# Motor_Cape.net
KiCad netlist of a schematic drawn in EAGLE
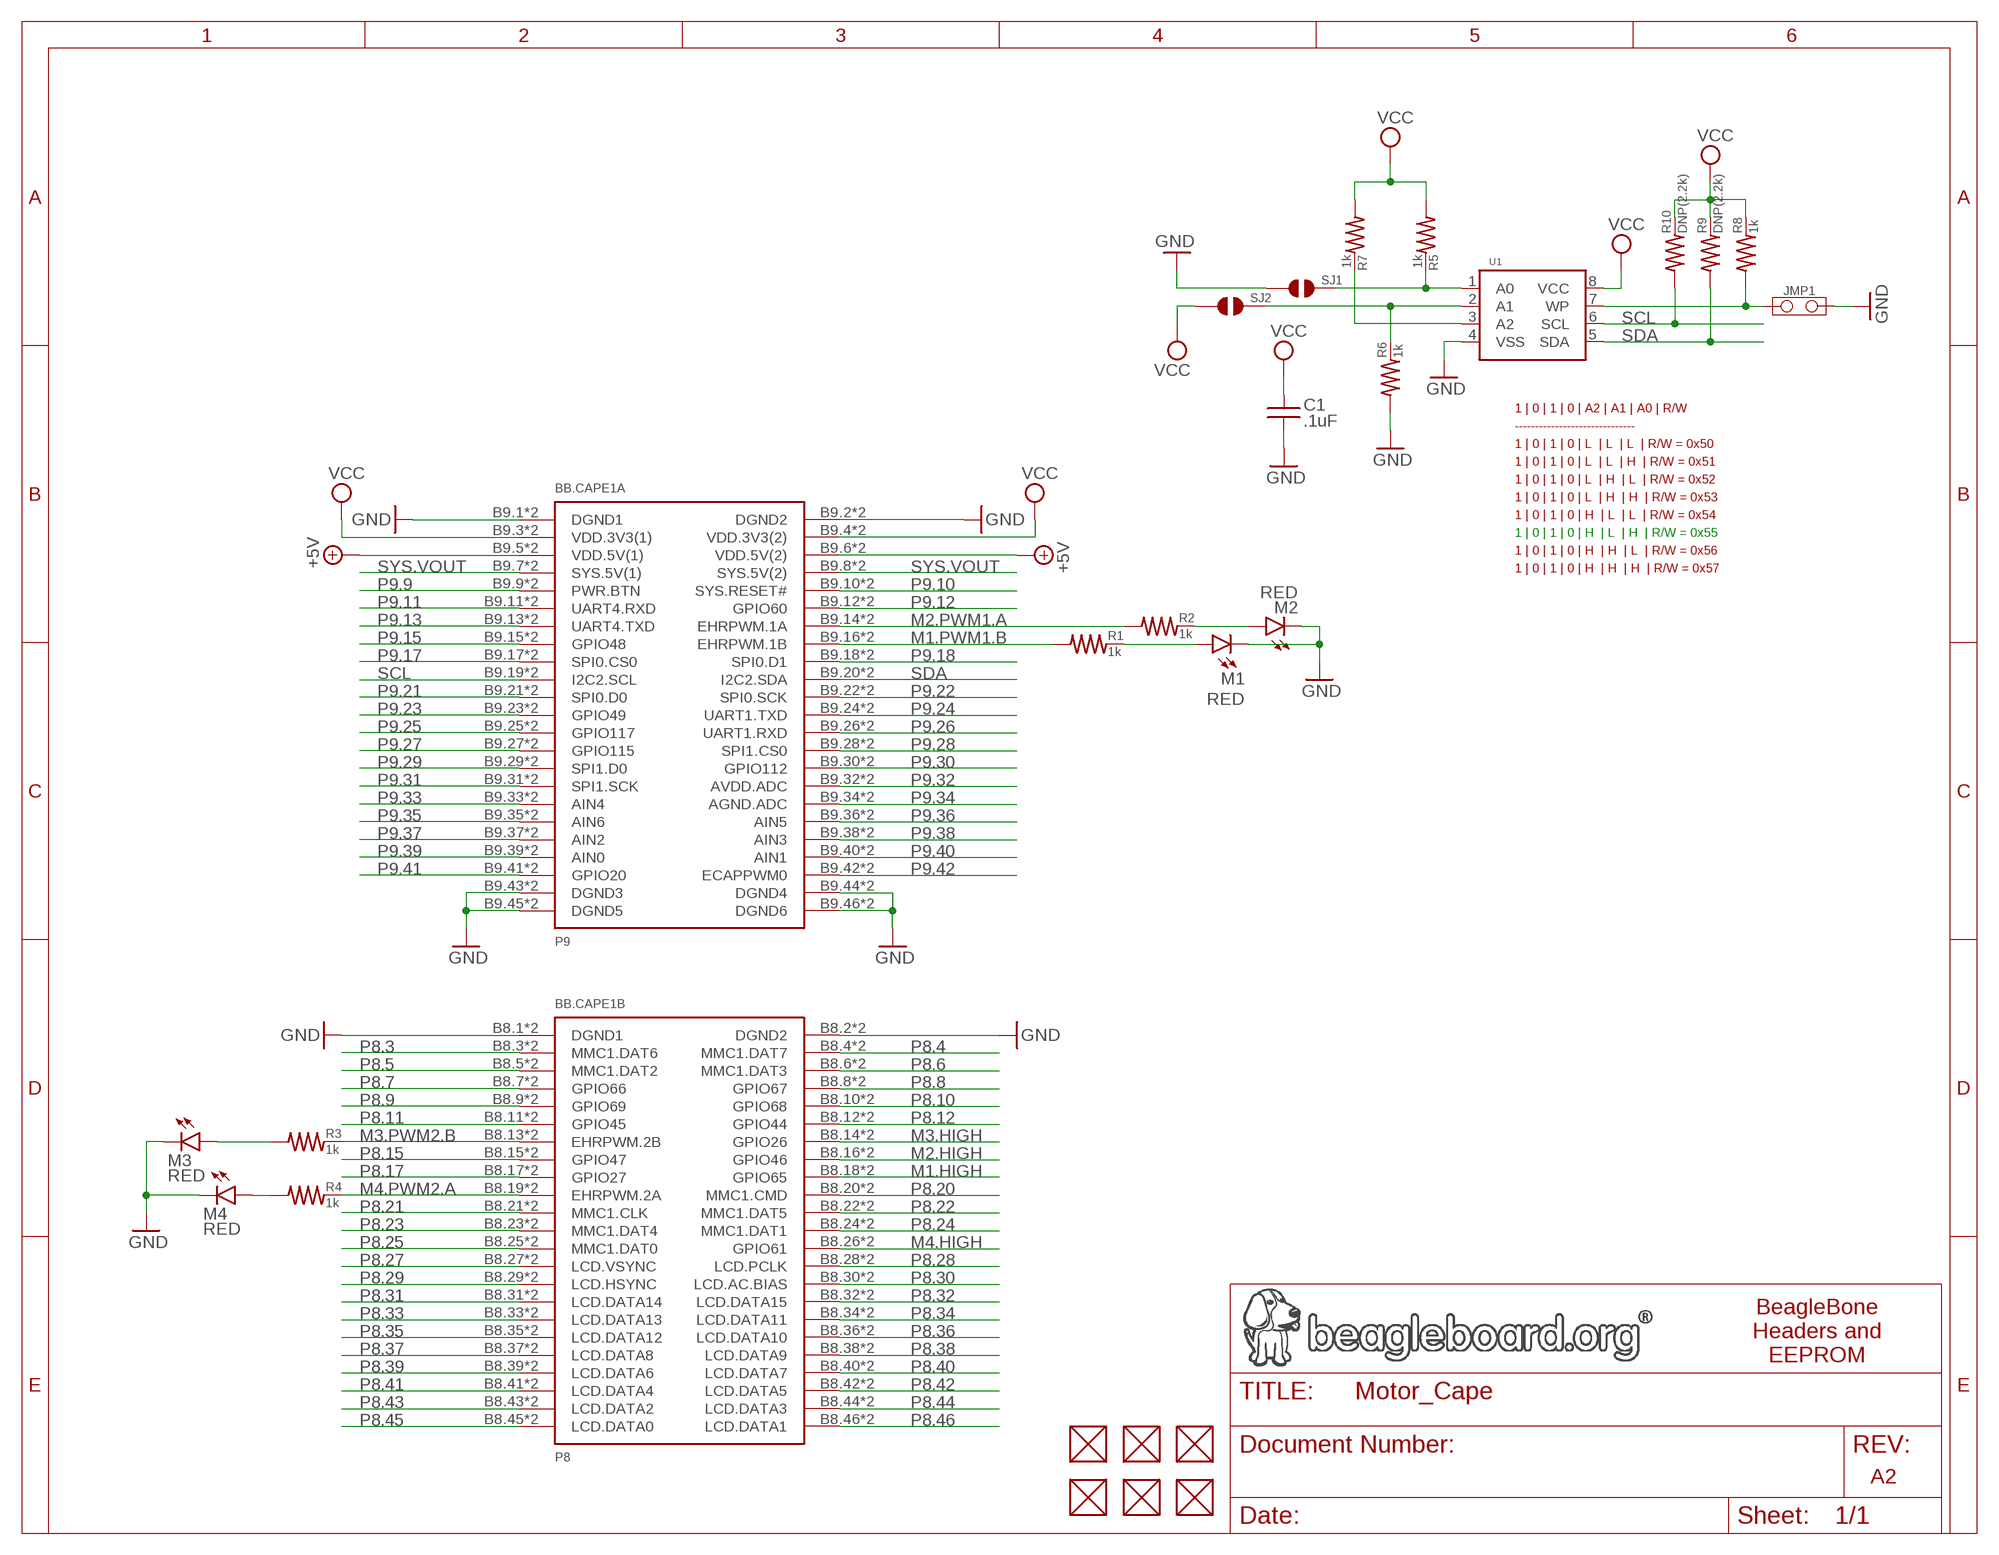
[diagram p0: schematic, sheet 1, part 1 of 2]
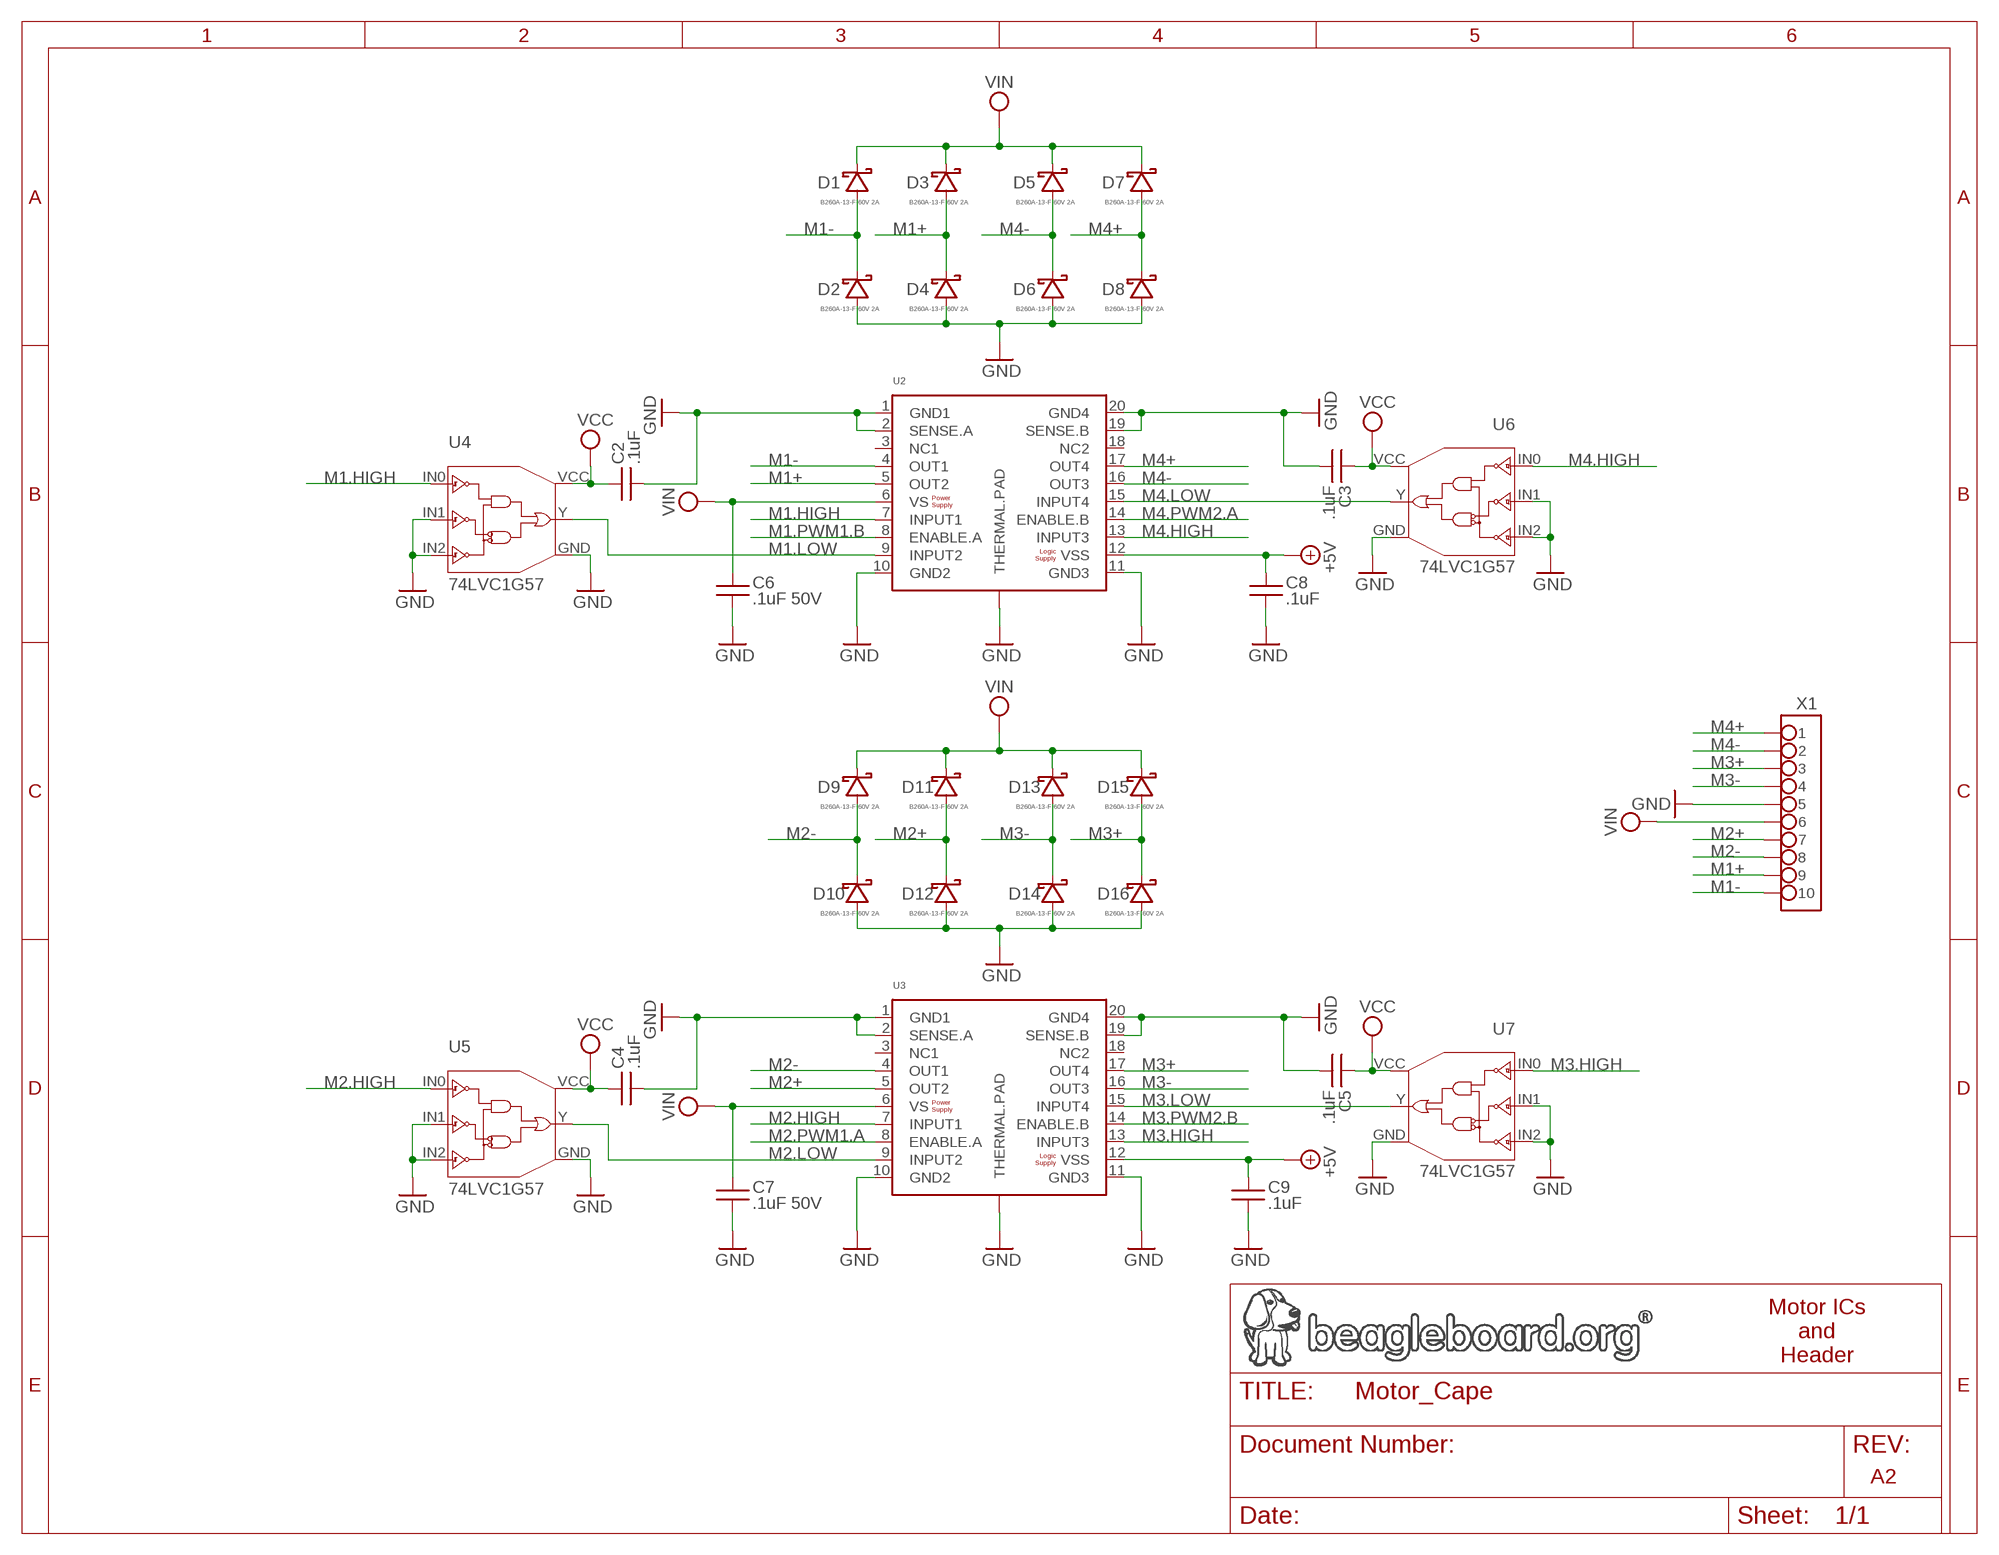
[diagram p1: schematic, sheet 1, part 2 of 2]

(export (version "E")
  (design (tool "Eeschema 10.0.6"))
  (components
    (comp (ref "BB.CAPE1")
      (value "BEAGLEBONE.CAPE.TOP/BOTTOM-PADS")
      (footprint "eagle-import:BEAGLEBONE.CAPE.TOP_BOTTOM-PADS")
      (libsource (lib "eagle-import") (part "BEAGLEBONE.CAPE.TOP/BOTTOM-PADS"))
    )
    (comp (ref "C1")
      (value ".1uF")
      (footprint "eagle-import:0402")
      (libsource (lib "eagle-import") (part "CAPACITOR-(INCH)-0402"))
    )
    (comp (ref "C2")
      (value ".1uF")
      (footprint "eagle-import:0402")
      (libsource (lib "eagle-import") (part "CAPACITOR-(INCH)-0402"))
    )
    (comp (ref "C3")
      (value ".1uF")
      (footprint "eagle-import:0402")
      (libsource (lib "eagle-import") (part "CAPACITOR-(INCH)-0402"))
    )
    (comp (ref "C4")
      (value ".1uF")
      (footprint "eagle-import:0402")
      (libsource (lib "eagle-import") (part "CAPACITOR-(INCH)-0402"))
    )
    (comp (ref "C5")
      (value ".1uF")
      (footprint "eagle-import:0402")
      (libsource (lib "eagle-import") (part "CAPACITOR-(INCH)-0402"))
    )
    (comp (ref "C6")
      (value ".1uF 50V")
      (footprint "eagle-import:0603")
      (libsource (lib "eagle-import") (part "CAPACITOR-(INCH)-0603"))
    )
    (comp (ref "C7")
      (value ".1uF 50V")
      (footprint "eagle-import:0603")
      (libsource (lib "eagle-import") (part "CAPACITOR-(INCH)-0603"))
    )
    (comp (ref "C8")
      (value ".1uF")
      (footprint "eagle-import:0402")
      (libsource (lib "eagle-import") (part "CAPACITOR-(INCH)-0402"))
    )
    (comp (ref "C9")
      (value ".1uF")
      (footprint "eagle-import:0402")
      (libsource (lib "eagle-import") (part "CAPACITOR-(INCH)-0402"))
    )
    (comp (ref "D1")
      (value "B260A-13-F 60V 2A")
      (footprint "eagle-import:SMA(DIODES)")
      (libsource (lib "eagle-import") (part "DIODE-SCHOTTKY-(DIODES)-SMA"))
    )
    (comp (ref "D2")
      (value "B260A-13-F 60V 2A")
      (footprint "eagle-import:SMA(DIODES)")
      (libsource (lib "eagle-import") (part "DIODE-SCHOTTKY-(DIODES)-SMA"))
    )
    (comp (ref "D3")
      (value "B260A-13-F 60V 2A")
      (footprint "eagle-import:SMA(DIODES)")
      (libsource (lib "eagle-import") (part "DIODE-SCHOTTKY-(DIODES)-SMA"))
    )
    (comp (ref "D4")
      (value "B260A-13-F 60V 2A")
      (footprint "eagle-import:SMA(DIODES)")
      (libsource (lib "eagle-import") (part "DIODE-SCHOTTKY-(DIODES)-SMA"))
    )
    (comp (ref "D5")
      (value "B260A-13-F 60V 2A")
      (footprint "eagle-import:SMA(DIODES)")
      (libsource (lib "eagle-import") (part "DIODE-SCHOTTKY-(DIODES)-SMA"))
    )
    (comp (ref "D6")
      (value "B260A-13-F 60V 2A")
      (footprint "eagle-import:SMA(DIODES)")
      (libsource (lib "eagle-import") (part "DIODE-SCHOTTKY-(DIODES)-SMA"))
    )
    (comp (ref "D7")
      (value "B260A-13-F 60V 2A")
      (footprint "eagle-import:SMA(DIODES)")
      (libsource (lib "eagle-import") (part "DIODE-SCHOTTKY-(DIODES)-SMA"))
    )
    (comp (ref "D8")
      (value "B260A-13-F 60V 2A")
      (footprint "eagle-import:SMA(DIODES)")
      (libsource (lib "eagle-import") (part "DIODE-SCHOTTKY-(DIODES)-SMA"))
    )
    (comp (ref "D9")
      (value "B260A-13-F 60V 2A")
      (footprint "eagle-import:SMA(DIODES)")
      (libsource (lib "eagle-import") (part "DIODE-SCHOTTKY-(DIODES)-SMA"))
    )
    (comp (ref "D10")
      (value "B260A-13-F 60V 2A")
      (footprint "eagle-import:SMA(DIODES)")
      (libsource (lib "eagle-import") (part "DIODE-SCHOTTKY-(DIODES)-SMA"))
    )
    (comp (ref "D11")
      (value "B260A-13-F 60V 2A")
      (footprint "eagle-import:SMA(DIODES)")
      (libsource (lib "eagle-import") (part "DIODE-SCHOTTKY-(DIODES)-SMA"))
    )
    (comp (ref "D12")
      (value "B260A-13-F 60V 2A")
      (footprint "eagle-import:SMA(DIODES)")
      (libsource (lib "eagle-import") (part "DIODE-SCHOTTKY-(DIODES)-SMA"))
    )
    (comp (ref "D13")
      (value "B260A-13-F 60V 2A")
      (footprint "eagle-import:SMA(DIODES)")
      (libsource (lib "eagle-import") (part "DIODE-SCHOTTKY-(DIODES)-SMA"))
    )
    (comp (ref "D14")
      (value "B260A-13-F 60V 2A")
      (footprint "eagle-import:SMA(DIODES)")
      (libsource (lib "eagle-import") (part "DIODE-SCHOTTKY-(DIODES)-SMA"))
    )
    (comp (ref "D15")
      (value "B260A-13-F 60V 2A")
      (footprint "eagle-import:SMA(DIODES)")
      (libsource (lib "eagle-import") (part "DIODE-SCHOTTKY-(DIODES)-SMA"))
    )
    (comp (ref "D16")
      (value "B260A-13-F 60V 2A")
      (footprint "eagle-import:SMA(DIODES)")
      (libsource (lib "eagle-import") (part "DIODE-SCHOTTKY-(DIODES)-SMA"))
    )
    (comp (ref "FUD1")
      (value "FIDUCIAL")
      (footprint "eagle-import:FIDUCIAL_40MIL")
      (libsource (lib "eagle-import") (part "FIDUCIAL"))
    )
    (comp (ref "FUD2")
      (value "FIDUCIAL")
      (footprint "eagle-import:FIDUCIAL_40MIL")
      (libsource (lib "eagle-import") (part "FIDUCIAL"))
    )
    (comp (ref "FUD3")
      (value "FIDUCIAL")
      (footprint "eagle-import:FIDUCIAL_40MIL")
      (libsource (lib "eagle-import") (part "FIDUCIAL"))
    )
    (comp (ref "FUD4")
      (value "FIDUCIAL")
      (footprint "eagle-import:FIDUCIAL_40MIL")
      (libsource (lib "eagle-import") (part "FIDUCIAL"))
    )
    (comp (ref "FUD5")
      (value "FIDUCIAL")
      (footprint "eagle-import:FIDUCIAL_40MIL")
      (libsource (lib "eagle-import") (part "FIDUCIAL"))
    )
    (comp (ref "FUD6")
      (value "FIDUCIAL")
      (footprint "eagle-import:FIDUCIAL_40MIL")
      (libsource (lib "eagle-import") (part "FIDUCIAL"))
    )
    (comp (ref "JMP1")
      (value "JUMPER-(X2)")
      (footprint "eagle-import:JUMPER-(X2)")
      (libsource (lib "eagle-import") (part "JUMPER-(X2)"))
    )
    (comp (ref "M1")
      (value "RED")
      (footprint "eagle-import:0805-LED")
      (libsource (lib "eagle-import") (part "LED-(INCH)-0805"))
    )
    (comp (ref "M2")
      (value "RED")
      (footprint "eagle-import:0805-LED")
      (libsource (lib "eagle-import") (part "LED-(INCH)-0805"))
    )
    (comp (ref "M3")
      (value "RED")
      (footprint "eagle-import:0805-LED")
      (libsource (lib "eagle-import") (part "LED-(INCH)-0805"))
    )
    (comp (ref "M4")
      (value "RED")
      (footprint "eagle-import:0805-LED")
      (libsource (lib "eagle-import") (part "LED-(INCH)-0805"))
    )
    (comp (ref "R1")
      (value "1k")
      (footprint "eagle-import:0402")
      (libsource (lib "eagle-import") (part "RESISTOR-(INCH)-0402"))
    )
    (comp (ref "R2")
      (value "1k")
      (footprint "eagle-import:0402")
      (libsource (lib "eagle-import") (part "RESISTOR-(INCH)-0402"))
    )
    (comp (ref "R3")
      (value "1k")
      (footprint "eagle-import:0402")
      (libsource (lib "eagle-import") (part "RESISTOR-(INCH)-0402"))
    )
    (comp (ref "R4")
      (value "1k")
      (footprint "eagle-import:0402")
      (libsource (lib "eagle-import") (part "RESISTOR-(INCH)-0402"))
    )
    (comp (ref "R5")
      (value "1k")
      (footprint "eagle-import:0402")
      (libsource (lib "eagle-import") (part "RESISTOR-(INCH)-0402"))
    )
    (comp (ref "R6")
      (value "1k")
      (footprint "eagle-import:0402")
      (libsource (lib "eagle-import") (part "RESISTOR-(INCH)-0402"))
    )
    (comp (ref "R7")
      (value "1k")
      (footprint "eagle-import:0402")
      (libsource (lib "eagle-import") (part "RESISTOR-(INCH)-0402"))
    )
    (comp (ref "R8")
      (value "1k")
      (footprint "eagle-import:0402")
      (libsource (lib "eagle-import") (part "RESISTOR-(INCH)-0402"))
    )
    (comp (ref "R9")
      (value "DNP(2.2k)")
      (footprint "eagle-import:0402")
      (libsource (lib "eagle-import") (part "RESISTOR-(INCH)-0402"))
    )
    (comp (ref "R10")
      (value "DNP(2.2k)")
      (footprint "eagle-import:0402")
      (libsource (lib "eagle-import") (part "RESISTOR-(INCH)-0402"))
    )
    (comp (ref "SJ1")
      (value "SOLDER.JOINT-(INCH)-0402")
      (footprint "eagle-import:SOLDER.JOINT(0402)")
      (libsource (lib "eagle-import") (part "SOLDER.JOINT-(INCH)-0402"))
    )
    (comp (ref "SJ2")
      (value "SOLDER.JOINT-(INCH)-0402")
      (footprint "eagle-import:SOLDER.JOINT(0402)")
      (libsource (lib "eagle-import") (part "SOLDER.JOINT-(INCH)-0402"))
    )
    (comp (ref "U1")
      (value "CAT24C32")
      (footprint "eagle-import:UDFN8,2X3(ON-SEMI)")
      (libsource (lib "eagle-import") (part "CAT24C32"))
    )
    (comp (ref "U2")
      (value "ST-L298-TP(VERSION.A)-W/TV")
      (footprint "eagle-import:POWER.SO-20(ST)-A.W_TV")
      (libsource (lib "eagle-import") (part "ST-L298-TP(VERSION.A)-W/TV"))
    )
    (comp (ref "U3")
      (value "ST-L298-TP(VERSION.A)-W/TV")
      (footprint "eagle-import:POWER.SO-20(ST)-A.W_TV")
      (libsource (lib "eagle-import") (part "ST-L298-TP(VERSION.A)-W/TV"))
    )
    (comp (ref "U4")
      (value "74LVC1G57")
      (footprint "eagle-import:SOT-23-6")
      (libsource (lib "eagle-import") (part "74LVC1G57"))
    )
    (comp (ref "U5")
      (value "74LVC1G57")
      (footprint "eagle-import:SOT-23-6")
      (libsource (lib "eagle-import") (part "74LVC1G57"))
    )
    (comp (ref "U6")
      (value "74LVC1G57")
      (footprint "eagle-import:SOT-23-6")
      (libsource (lib "eagle-import") (part "74LVC1G57"))
    )
    (comp (ref "U7")
      (value "74LVC1G57")
      (footprint "eagle-import:SOT-23-6")
      (libsource (lib "eagle-import") (part "74LVC1G57"))
    )
    (comp (ref "X1")
      (value "TB-10TERM-150MIL.PITCH")
      (footprint "eagle-import:TERMINAL.BLOCK-10TERM-150MIL.PITCH")
      (libsource (lib "eagle-import") (part "TB-10TERM-150MIL.PITCH"))
    )
  )
  (nets
    (net (code "1") (name "+5V") (class "Default")
      (node (ref "BB.CAPE1") (pin "B9.5") (pinfunction "VDD.5V(1)_B9.5") (pintype "bidirectional"))
      (node (ref "BB.CAPE1") (pin "B9.6") (pinfunction "VDD.5V(2)_B9.6") (pintype "bidirectional"))
      (node (ref "BB.CAPE1") (pin "T9.5") (pinfunction "VDD.5V(1)_T9.5") (pintype "bidirectional"))
      (node (ref "BB.CAPE1") (pin "T9.6") (pinfunction "VDD.5V(2)_T9.6") (pintype "bidirectional"))
      (node (ref "C8") (pin "1") (pinfunction "1_1") (pintype "bidirectional"))
      (node (ref "C9") (pin "1") (pinfunction "1_1") (pintype "bidirectional"))
      (node (ref "U2") (pin "12") (pinfunction "VSS_12") (pintype "bidirectional"))
      (node (ref "U3") (pin "12") (pinfunction "VSS_12") (pintype "bidirectional"))
    )
    (net (code "2") (name "/M1+") (class "Default")
      (node (ref "D3") (pin "A") (pinfunction "ANODE_A") (pintype "bidirectional"))
      (node (ref "D4") (pin "K") (pinfunction "CATHODE_K") (pintype "bidirectional"))
      (node (ref "U2") (pin "5") (pinfunction "OUT2_5") (pintype "bidirectional"))
      (node (ref "X1") (pin "9") (pinfunction "9_9") (pintype "bidirectional"))
    )
    (net (code "3") (name "/M1-") (class "Default")
      (node (ref "D1") (pin "A") (pinfunction "ANODE_A") (pintype "bidirectional"))
      (node (ref "D2") (pin "K") (pinfunction "CATHODE_K") (pintype "bidirectional"))
      (node (ref "U2") (pin "4") (pinfunction "OUT1_4") (pintype "bidirectional"))
      (node (ref "X1") (pin "10") (pinfunction "10_10") (pintype "bidirectional"))
    )
    (net (code "4") (name "/M1.HIGH") (class "Default")
      (node (ref "BB.CAPE1") (pin "B8.18") (pinfunction "GPIO65_B8.18") (pintype "bidirectional"))
      (node (ref "BB.CAPE1") (pin "T8.18") (pinfunction "GPIO65_T8.18") (pintype "bidirectional"))
      (node (ref "U2") (pin "7") (pinfunction "INPUT1_7") (pintype "bidirectional"))
      (node (ref "U4") (pin "IN0") (pinfunction "IN0_IN0") (pintype "bidirectional"))
    )
    (net (code "5") (name "/M1.LOW") (class "Default")
      (node (ref "U2") (pin "9") (pinfunction "INPUT2_9") (pintype "bidirectional"))
      (node (ref "U4") (pin "Y") (pinfunction "Y_Y") (pintype "bidirectional"))
    )
    (net (code "6") (name "/M1.PWM1.B") (class "Default")
      (node (ref "BB.CAPE1") (pin "B9.16") (pinfunction "EHRPWM.1B_B9.16") (pintype "bidirectional"))
      (node (ref "BB.CAPE1") (pin "T9.16") (pinfunction "EHRPWM.1B_T9.16") (pintype "bidirectional"))
      (node (ref "R1") (pin "1") (pinfunction "1_1") (pintype "bidirectional"))
      (node (ref "U2") (pin "8") (pinfunction "ENABLE.A_8") (pintype "bidirectional"))
    )
    (net (code "7") (name "/M2+") (class "Default")
      (node (ref "D11") (pin "A") (pinfunction "ANODE_A") (pintype "bidirectional"))
      (node (ref "D12") (pin "K") (pinfunction "CATHODE_K") (pintype "bidirectional"))
      (node (ref "U3") (pin "5") (pinfunction "OUT2_5") (pintype "bidirectional"))
      (node (ref "X1") (pin "7") (pinfunction "7_7") (pintype "bidirectional"))
    )
    (net (code "8") (name "/M2-") (class "Default")
      (node (ref "D10") (pin "K") (pinfunction "CATHODE_K") (pintype "bidirectional"))
      (node (ref "D9") (pin "A") (pinfunction "ANODE_A") (pintype "bidirectional"))
      (node (ref "U3") (pin "4") (pinfunction "OUT1_4") (pintype "bidirectional"))
      (node (ref "X1") (pin "8") (pinfunction "8_8") (pintype "bidirectional"))
    )
    (net (code "9") (name "/M2.HIGH") (class "Default")
      (node (ref "BB.CAPE1") (pin "B8.16") (pinfunction "GPIO46_B8.16") (pintype "bidirectional"))
      (node (ref "BB.CAPE1") (pin "T8.16") (pinfunction "GPIO46_T8.16") (pintype "bidirectional"))
      (node (ref "U3") (pin "7") (pinfunction "INPUT1_7") (pintype "bidirectional"))
      (node (ref "U5") (pin "IN0") (pinfunction "IN0_IN0") (pintype "bidirectional"))
    )
    (net (code "10") (name "/M2.LOW") (class "Default")
      (node (ref "U3") (pin "9") (pinfunction "INPUT2_9") (pintype "bidirectional"))
      (node (ref "U5") (pin "Y") (pinfunction "Y_Y") (pintype "bidirectional"))
    )
    (net (code "11") (name "/M2.PWM1.A") (class "Default")
      (node (ref "BB.CAPE1") (pin "B9.14") (pinfunction "EHRPWM.1A_B9.14") (pintype "bidirectional"))
      (node (ref "BB.CAPE1") (pin "T9.14") (pinfunction "EHRPWM.1A_T9.14") (pintype "bidirectional"))
      (node (ref "R2") (pin "1") (pinfunction "1_1") (pintype "bidirectional"))
      (node (ref "U3") (pin "8") (pinfunction "ENABLE.A_8") (pintype "bidirectional"))
    )
    (net (code "12") (name "/M3+") (class "Default")
      (node (ref "D15") (pin "A") (pinfunction "ANODE_A") (pintype "bidirectional"))
      (node (ref "D16") (pin "K") (pinfunction "CATHODE_K") (pintype "bidirectional"))
      (node (ref "U3") (pin "17") (pinfunction "OUT4_17") (pintype "bidirectional"))
      (node (ref "X1") (pin "3") (pinfunction "3_3") (pintype "bidirectional"))
    )
    (net (code "13") (name "/M3-") (class "Default")
      (node (ref "D13") (pin "A") (pinfunction "ANODE_A") (pintype "bidirectional"))
      (node (ref "D14") (pin "K") (pinfunction "CATHODE_K") (pintype "bidirectional"))
      (node (ref "U3") (pin "16") (pinfunction "OUT3_16") (pintype "bidirectional"))
      (node (ref "X1") (pin "4") (pinfunction "4_4") (pintype "bidirectional"))
    )
    (net (code "14") (name "/M3.HIGH") (class "Default")
      (node (ref "BB.CAPE1") (pin "B8.14") (pinfunction "GPIO26_B8.14") (pintype "bidirectional"))
      (node (ref "BB.CAPE1") (pin "T8.14") (pinfunction "GPIO26_T8.14") (pintype "bidirectional"))
      (node (ref "U3") (pin "13") (pinfunction "INPUT3_13") (pintype "bidirectional"))
      (node (ref "U7") (pin "IN0") (pinfunction "IN0_IN0") (pintype "bidirectional"))
    )
    (net (code "15") (name "/M3.LOW") (class "Default")
      (node (ref "U3") (pin "15") (pinfunction "INPUT4_15") (pintype "bidirectional"))
      (node (ref "U7") (pin "Y") (pinfunction "Y_Y") (pintype "bidirectional"))
    )
    (net (code "16") (name "/M3.PWM2.B") (class "Default")
      (node (ref "BB.CAPE1") (pin "B8.13") (pinfunction "EHRPWM.2B_B8.13") (pintype "bidirectional"))
      (node (ref "BB.CAPE1") (pin "T8.13") (pinfunction "EHRPWM.2B_T8.13") (pintype "bidirectional"))
      (node (ref "R3") (pin "2") (pinfunction "2_2") (pintype "bidirectional"))
      (node (ref "U3") (pin "14") (pinfunction "ENABLE.B_14") (pintype "bidirectional"))
    )
    (net (code "17") (name "/M4+") (class "Default")
      (node (ref "D7") (pin "A") (pinfunction "ANODE_A") (pintype "bidirectional"))
      (node (ref "D8") (pin "K") (pinfunction "CATHODE_K") (pintype "bidirectional"))
      (node (ref "U2") (pin "17") (pinfunction "OUT4_17") (pintype "bidirectional"))
      (node (ref "X1") (pin "1") (pinfunction "1_1") (pintype "bidirectional"))
    )
    (net (code "18") (name "/M4-") (class "Default")
      (node (ref "D5") (pin "A") (pinfunction "ANODE_A") (pintype "bidirectional"))
      (node (ref "D6") (pin "K") (pinfunction "CATHODE_K") (pintype "bidirectional"))
      (node (ref "U2") (pin "16") (pinfunction "OUT3_16") (pintype "bidirectional"))
      (node (ref "X1") (pin "2") (pinfunction "2_2") (pintype "bidirectional"))
    )
    (net (code "19") (name "/M4.HIGH") (class "Default")
      (node (ref "BB.CAPE1") (pin "B8.26") (pinfunction "GPIO61_B8.26") (pintype "bidirectional"))
      (node (ref "BB.CAPE1") (pin "T8.26") (pinfunction "GPIO61_T8.26") (pintype "bidirectional"))
      (node (ref "U2") (pin "13") (pinfunction "INPUT3_13") (pintype "bidirectional"))
      (node (ref "U6") (pin "IN0") (pinfunction "IN0_IN0") (pintype "bidirectional"))
    )
    (net (code "20") (name "/M4.LOW") (class "Default")
      (node (ref "U2") (pin "15") (pinfunction "INPUT4_15") (pintype "bidirectional"))
      (node (ref "U6") (pin "Y") (pinfunction "Y_Y") (pintype "bidirectional"))
    )
    (net (code "21") (name "/M4.PWM2.A") (class "Default")
      (node (ref "BB.CAPE1") (pin "B8.19") (pinfunction "EHRPWM.2A_B8.19") (pintype "bidirectional"))
      (node (ref "BB.CAPE1") (pin "T8.19") (pinfunction "EHRPWM.2A_T8.19") (pintype "bidirectional"))
      (node (ref "R4") (pin "2") (pinfunction "2_2") (pintype "bidirectional"))
      (node (ref "U2") (pin "14") (pinfunction "ENABLE.B_14") (pintype "bidirectional"))
    )
    (net (code "22") (name "/P8.3") (class "Default")
      (node (ref "BB.CAPE1") (pin "B8.3") (pinfunction "MMC1.DAT6_B8.3") (pintype "bidirectional"))
      (node (ref "BB.CAPE1") (pin "T8.3") (pinfunction "MMC1.DAT6_T8.3") (pintype "bidirectional"))
    )
    (net (code "23") (name "/P8.4") (class "Default")
      (node (ref "BB.CAPE1") (pin "B8.4") (pinfunction "MMC1.DAT7_B8.4") (pintype "bidirectional"))
      (node (ref "BB.CAPE1") (pin "T8.4") (pinfunction "MMC1.DAT7_T8.4") (pintype "bidirectional"))
    )
    (net (code "24") (name "/P8.5") (class "Default")
      (node (ref "BB.CAPE1") (pin "B8.5") (pinfunction "MMC1.DAT2_B8.5") (pintype "bidirectional"))
      (node (ref "BB.CAPE1") (pin "T8.5") (pinfunction "MMC1.DAT2_T8.5") (pintype "bidirectional"))
    )
    (net (code "25") (name "/P8.6") (class "Default")
      (node (ref "BB.CAPE1") (pin "B8.6") (pinfunction "MMC1.DAT3_B8.6") (pintype "bidirectional"))
      (node (ref "BB.CAPE1") (pin "T8.6") (pinfunction "MMC1.DAT3_T8.6") (pintype "bidirectional"))
    )
    (net (code "26") (name "/P8.7") (class "Default")
      (node (ref "BB.CAPE1") (pin "B8.7") (pinfunction "GPIO66_B8.7") (pintype "bidirectional"))
      (node (ref "BB.CAPE1") (pin "T8.7") (pinfunction "GPIO66_T8.7") (pintype "bidirectional"))
    )
    (net (code "27") (name "/P8.8") (class "Default")
      (node (ref "BB.CAPE1") (pin "B8.8") (pinfunction "GPIO67_B8.8") (pintype "bidirectional"))
      (node (ref "BB.CAPE1") (pin "T8.8") (pinfunction "GPIO67_T8.8") (pintype "bidirectional"))
    )
    (net (code "28") (name "/P8.9") (class "Default")
      (node (ref "BB.CAPE1") (pin "B8.9") (pinfunction "GPIO69_B8.9") (pintype "bidirectional"))
      (node (ref "BB.CAPE1") (pin "T8.9") (pinfunction "GPIO69_T8.9") (pintype "bidirectional"))
    )
    (net (code "29") (name "/P8.10") (class "Default")
      (node (ref "BB.CAPE1") (pin "B8.10") (pinfunction "GPIO68_B8.10") (pintype "bidirectional"))
      (node (ref "BB.CAPE1") (pin "T8.10") (pinfunction "GPIO68_T8.10") (pintype "bidirectional"))
    )
    (net (code "30") (name "/P8.11") (class "Default")
      (node (ref "BB.CAPE1") (pin "B8.11") (pinfunction "GPIO45_B8.11") (pintype "bidirectional"))
      (node (ref "BB.CAPE1") (pin "T8.11") (pinfunction "GPIO45_T8.11") (pintype "bidirectional"))
    )
    (net (code "31") (name "/P8.12") (class "Default")
      (node (ref "BB.CAPE1") (pin "B8.12") (pinfunction "GPIO44_B8.12") (pintype "bidirectional"))
      (node (ref "BB.CAPE1") (pin "T8.12") (pinfunction "GPIO44_T8.12") (pintype "bidirectional"))
    )
    (net (code "32") (name "/P8.15") (class "Default")
      (node (ref "BB.CAPE1") (pin "B8.15") (pinfunction "GPIO47_B8.15") (pintype "bidirectional"))
      (node (ref "BB.CAPE1") (pin "T8.15") (pinfunction "GPIO47_T8.15") (pintype "bidirectional"))
    )
    (net (code "33") (name "/P8.17") (class "Default")
      (node (ref "BB.CAPE1") (pin "B8.17") (pinfunction "GPIO27_B8.17") (pintype "bidirectional"))
      (node (ref "BB.CAPE1") (pin "T8.17") (pinfunction "GPIO27_T8.17") (pintype "bidirectional"))
    )
    (net (code "34") (name "/P8.20") (class "Default")
      (node (ref "BB.CAPE1") (pin "B8.20") (pinfunction "MMC1.CMD_B8.20") (pintype "bidirectional"))
      (node (ref "BB.CAPE1") (pin "T8.20") (pinfunction "MMC1.CMD_T8.20") (pintype "bidirectional"))
    )
    (net (code "35") (name "/P8.21") (class "Default")
      (node (ref "BB.CAPE1") (pin "B8.21") (pinfunction "MMC1.CLK_B8.21") (pintype "bidirectional"))
      (node (ref "BB.CAPE1") (pin "T8.21") (pinfunction "MMC1.CLK_T8.21") (pintype "bidirectional"))
    )
    (net (code "36") (name "/P8.22") (class "Default")
      (node (ref "BB.CAPE1") (pin "B8.22") (pinfunction "MMC1.DAT5_B8.22") (pintype "bidirectional"))
      (node (ref "BB.CAPE1") (pin "T8.22") (pinfunction "MMC1.DAT5_T8.22") (pintype "bidirectional"))
    )
    (net (code "37") (name "/P8.23") (class "Default")
      (node (ref "BB.CAPE1") (pin "B8.23") (pinfunction "MMC1.DAT4_B8.23") (pintype "bidirectional"))
      (node (ref "BB.CAPE1") (pin "T8.23") (pinfunction "MMC1.DAT4_T8.23") (pintype "bidirectional"))
    )
    (net (code "38") (name "/P8.24") (class "Default")
      (node (ref "BB.CAPE1") (pin "B8.24") (pinfunction "MMC1.DAT1_B8.24") (pintype "bidirectional"))
      (node (ref "BB.CAPE1") (pin "T8.24") (pinfunction "MMC1.DAT1_T8.24") (pintype "bidirectional"))
    )
    (net (code "39") (name "/P8.25") (class "Default")
      (node (ref "BB.CAPE1") (pin "B8.25") (pinfunction "MMC1.DAT0_B8.25") (pintype "bidirectional"))
      (node (ref "BB.CAPE1") (pin "T8.25") (pinfunction "MMC1.DAT0_T8.25") (pintype "bidirectional"))
    )
    (net (code "40") (name "/P8.27") (class "Default")
      (node (ref "BB.CAPE1") (pin "B8.27") (pinfunction "LCD.VSYNC_B8.27") (pintype "bidirectional"))
      (node (ref "BB.CAPE1") (pin "T8.27") (pinfunction "LCD.VSYNC_T8.27") (pintype "bidirectional"))
    )
    (net (code "41") (name "/P8.28") (class "Default")
      (node (ref "BB.CAPE1") (pin "B8.28") (pinfunction "LCD.PCLK_B8.28") (pintype "bidirectional"))
      (node (ref "BB.CAPE1") (pin "T8.28") (pinfunction "LCD.PCLK_T8.28") (pintype "bidirectional"))
    )
    (net (code "42") (name "/P8.29") (class "Default")
      (node (ref "BB.CAPE1") (pin "B8.29") (pinfunction "LCD.HSYNC_B8.29") (pintype "bidirectional"))
      (node (ref "BB.CAPE1") (pin "T8.29") (pinfunction "LCD.HSYNC_T8.29") (pintype "bidirectional"))
    )
    (net (code "43") (name "/P8.30") (class "Default")
      (node (ref "BB.CAPE1") (pin "B8.30") (pinfunction "LCD.AC.BIAS_B8.30") (pintype "bidirectional"))
      (node (ref "BB.CAPE1") (pin "T8.30") (pinfunction "LCD.AC.BIAS_T8.30") (pintype "bidirectional"))
    )
    (net (code "44") (name "/P8.31") (class "Default")
      (node (ref "BB.CAPE1") (pin "B8.31") (pinfunction "LCD.DATA14_B8.31") (pintype "bidirectional"))
      (node (ref "BB.CAPE1") (pin "T8.31") (pinfunction "LCD.DATA14_T8.31") (pintype "bidirectional"))
    )
    (net (code "45") (name "/P8.32") (class "Default")
      (node (ref "BB.CAPE1") (pin "B8.32") (pinfunction "LCD.DATA15_B8.32") (pintype "bidirectional"))
      (node (ref "BB.CAPE1") (pin "T8.32") (pinfunction "LCD.DATA15_T8.32") (pintype "bidirectional"))
    )
    (net (code "46") (name "/P8.33") (class "Default")
      (node (ref "BB.CAPE1") (pin "B8.33") (pinfunction "LCD.DATA13_B8.33") (pintype "bidirectional"))
      (node (ref "BB.CAPE1") (pin "T8.33") (pinfunction "LCD.DATA13_T8.33") (pintype "bidirectional"))
    )
    (net (code "47") (name "/P8.34") (class "Default")
      (node (ref "BB.CAPE1") (pin "B8.34") (pinfunction "LCD.DATA11_B8.34") (pintype "bidirectional"))
      (node (ref "BB.CAPE1") (pin "T8.34") (pinfunction "LCD.DATA11_T8.34") (pintype "bidirectional"))
    )
    (net (code "48") (name "/P8.35") (class "Default")
      (node (ref "BB.CAPE1") (pin "B8.35") (pinfunction "LCD.DATA12_B8.35") (pintype "bidirectional"))
      (node (ref "BB.CAPE1") (pin "T8.35") (pinfunction "LCD.DATA12_T8.35") (pintype "bidirectional"))
    )
    (net (code "49") (name "/P8.36") (class "Default")
      (node (ref "BB.CAPE1") (pin "B8.36") (pinfunction "LCD.DATA10_B8.36") (pintype "bidirectional"))
      (node (ref "BB.CAPE1") (pin "T8.36") (pinfunction "LCD.DATA10_T8.36") (pintype "bidirectional"))
    )
    (net (code "50") (name "/P8.37") (class "Default")
      (node (ref "BB.CAPE1") (pin "B8.37") (pinfunction "LCD.DATA8_B8.37") (pintype "bidirectional"))
      (node (ref "BB.CAPE1") (pin "T8.37") (pinfunction "LCD.DATA8_T8.37") (pintype "bidirectional"))
    )
    (net (code "51") (name "/P8.38") (class "Default")
      (node (ref "BB.CAPE1") (pin "B8.38") (pinfunction "LCD.DATA9_B8.38") (pintype "bidirectional"))
      (node (ref "BB.CAPE1") (pin "T8.38") (pinfunction "LCD.DATA9_T8.38") (pintype "bidirectional"))
    )
    (net (code "52") (name "/P8.39") (class "Default")
      (node (ref "BB.CAPE1") (pin "B8.39") (pinfunction "LCD.DATA6_B8.39") (pintype "bidirectional"))
      (node (ref "BB.CAPE1") (pin "T8.39") (pinfunction "LCD.DATA6_T8.39") (pintype "bidirectional"))
    )
    (net (code "53") (name "/P8.40") (class "Default")
      (node (ref "BB.CAPE1") (pin "B8.40") (pinfunction "LCD.DATA7_B8.40") (pintype "bidirectional"))
      (node (ref "BB.CAPE1") (pin "T8.40") (pinfunction "LCD.DATA7_T8.40") (pintype "bidirectional"))
    )
    (net (code "54") (name "/P8.41") (class "Default")
      (node (ref "BB.CAPE1") (pin "B8.41") (pinfunction "LCD.DATA4_B8.41") (pintype "bidirectional"))
      (node (ref "BB.CAPE1") (pin "T8.41") (pinfunction "LCD.DATA4_T8.41") (pintype "bidirectional"))
    )
    (net (code "55") (name "/P8.42") (class "Default")
      (node (ref "BB.CAPE1") (pin "B8.42") (pinfunction "LCD.DATA5_B8.42") (pintype "bidirectional"))
      (node (ref "BB.CAPE1") (pin "T8.42") (pinfunction "LCD.DATA5_T8.42") (pintype "bidirectional"))
    )
    (net (code "56") (name "/P8.43") (class "Default")
      (node (ref "BB.CAPE1") (pin "B8.43") (pinfunction "LCD.DATA2_B8.43") (pintype "bidirectional"))
      (node (ref "BB.CAPE1") (pin "T8.43") (pinfunction "LCD.DATA2_T8.43") (pintype "bidirectional"))
    )
    (net (code "57") (name "/P8.44") (class "Default")
      (node (ref "BB.CAPE1") (pin "B8.44") (pinfunction "LCD.DATA3_B8.44") (pintype "bidirectional"))
      (node (ref "BB.CAPE1") (pin "T8.44") (pinfunction "LCD.DATA3_T8.44") (pintype "bidirectional"))
    )
    (net (code "58") (name "/P8.45") (class "Default")
      (node (ref "BB.CAPE1") (pin "B8.45") (pinfunction "LCD.DATA0_B8.45") (pintype "bidirectional"))
      (node (ref "BB.CAPE1") (pin "T8.45") (pinfunction "LCD.DATA0_T8.45") (pintype "bidirectional"))
    )
    (net (code "59") (name "/P8.46") (class "Default")
      (node (ref "BB.CAPE1") (pin "B8.46") (pinfunction "LCD.DATA1_B8.46") (pintype "bidirectional"))
      (node (ref "BB.CAPE1") (pin "T8.46") (pinfunction "LCD.DATA1_T8.46") (pintype "bidirectional"))
    )
    (net (code "60") (name "/P9.9") (class "Default")
      (node (ref "BB.CAPE1") (pin "B9.9") (pinfunction "PWR.BTN_B9.9") (pintype "bidirectional"))
      (node (ref "BB.CAPE1") (pin "T9.9") (pinfunction "PWR.BTN_T9.9") (pintype "bidirectional"))
    )
    (net (code "61") (name "/P9.10") (class "Default")
      (node (ref "BB.CAPE1") (pin "B9.10") (pinfunction "SYS.RESET#_B9.10") (pintype "bidirectional"))
      (node (ref "BB.CAPE1") (pin "T9.10") (pinfunction "SYS.RESET#_T9.10") (pintype "bidirectional"))
    )
    (net (code "62") (name "/P9.11") (class "Default")
      (node (ref "BB.CAPE1") (pin "B9.11") (pinfunction "UART4.RXD_B9.11") (pintype "bidirectional"))
      (node (ref "BB.CAPE1") (pin "T9.11") (pinfunction "UART4.RXD_T9.11") (pintype "bidirectional"))
    )
    (net (code "63") (name "/P9.12") (class "Default")
      (node (ref "BB.CAPE1") (pin "B9.12") (pinfunction "GPIO60_B9.12") (pintype "bidirectional"))
      (node (ref "BB.CAPE1") (pin "T9.12") (pinfunction "GPIO60_T9.12") (pintype "bidirectional"))
    )
    (net (code "64") (name "/P9.13") (class "Default")
      (node (ref "BB.CAPE1") (pin "B9.13") (pinfunction "UART4.TXD_B9.13") (pintype "bidirectional"))
      (node (ref "BB.CAPE1") (pin "T9.13") (pinfunction "UART4.TXD_T9.13") (pintype "bidirectional"))
    )
    (net (code "65") (name "/P9.15") (class "Default")
      (node (ref "BB.CAPE1") (pin "B9.15") (pinfunction "GPIO48_B9.15") (pintype "bidirectional"))
      (node (ref "BB.CAPE1") (pin "T9.15") (pinfunction "GPIO48_T9.15") (pintype "bidirectional"))
    )
    (net (code "66") (name "/P9.17") (class "Default")
      (node (ref "BB.CAPE1") (pin "B9.17") (pinfunction "SPI0.CS0_B9.17") (pintype "bidirectional"))
      (node (ref "BB.CAPE1") (pin "T9.17") (pinfunction "SPI0.CS0_T9.17") (pintype "bidirectional"))
    )
    (net (code "67") (name "/P9.18") (class "Default")
      (node (ref "BB.CAPE1") (pin "B9.18") (pinfunction "SPI0.D1_B9.18") (pintype "bidirectional"))
      (node (ref "BB.CAPE1") (pin "T9.18") (pinfunction "SPI0.D1_T9.18") (pintype "bidirectional"))
    )
    (net (code "68") (name "/P9.21") (class "Default")
      (node (ref "BB.CAPE1") (pin "B9.21") (pinfunction "SPI0.D0_B9.21") (pintype "bidirectional"))
      (node (ref "BB.CAPE1") (pin "T9.21") (pinfunction "SPI0.D0_T9.21") (pintype "bidirectional"))
    )
    (net (code "69") (name "/P9.22") (class "Default")
      (node (ref "BB.CAPE1") (pin "B9.22") (pinfunction "SPI0.SCK_B9.22") (pintype "bidirectional"))
      (node (ref "BB.CAPE1") (pin "T9.22") (pinfunction "SPI0.SCK_T9.22") (pintype "bidirectional"))
    )
    (net (code "70") (name "/P9.23") (class "Default")
      (node (ref "BB.CAPE1") (pin "B9.23") (pinfunction "GPIO49_B9.23") (pintype "bidirectional"))
      (node (ref "BB.CAPE1") (pin "T9.23") (pinfunction "GPIO49_T9.23") (pintype "bidirectional"))
    )
    (net (code "71") (name "/P9.24") (class "Default")
      (node (ref "BB.CAPE1") (pin "B9.24") (pinfunction "UART1.TXD_B9.24") (pintype "bidirectional"))
      (node (ref "BB.CAPE1") (pin "T9.24") (pinfunction "UART1.TXD_T9.24") (pintype "bidirectional"))
    )
    (net (code "72") (name "/P9.25") (class "Default")
      (node (ref "BB.CAPE1") (pin "B9.25") (pinfunction "GPIO117_B9.25") (pintype "bidirectional"))
      (node (ref "BB.CAPE1") (pin "T9.25") (pinfunction "GPIO117_T9.25") (pintype "bidirectional"))
    )
    (net (code "73") (name "/P9.26") (class "Default")
      (node (ref "BB.CAPE1") (pin "B9.26") (pinfunction "UART1.RXD_B9.26") (pintype "bidirectional"))
      (node (ref "BB.CAPE1") (pin "T9.26") (pinfunction "UART1.RXD_T9.26") (pintype "bidirectional"))
    )
    (net (code "74") (name "/P9.27") (class "Default")
      (node (ref "BB.CAPE1") (pin "B9.27") (pinfunction "GPIO115_B9.27") (pintype "bidirectional"))
      (node (ref "BB.CAPE1") (pin "T9.27") (pinfunction "GPIO115_T9.27") (pintype "bidirectional"))
    )
    (net (code "75") (name "/P9.28") (class "Default")
      (node (ref "BB.CAPE1") (pin "B9.28") (pinfunction "SPI1.CS0_B9.28") (pintype "bidirectional"))
      (node (ref "BB.CAPE1") (pin "T9.28") (pinfunction "SPI1.CS0_T9.28") (pintype "bidirectional"))
    )
    (net (code "76") (name "/P9.29") (class "Default")
      (node (ref "BB.CAPE1") (pin "B9.29") (pinfunction "SPI1.D0_B9.29") (pintype "bidirectional"))
      (node (ref "BB.CAPE1") (pin "T9.29") (pinfunction "SPI1.D0_T9.29") (pintype "bidirectional"))
    )
    (net (code "77") (name "/P9.30") (class "Default")
      (node (ref "BB.CAPE1") (pin "B9.30") (pinfunction "GPIO112_B9.30") (pintype "bidirectional"))
      (node (ref "BB.CAPE1") (pin "T9.30") (pinfunction "GPIO112_T9.30") (pintype "bidirectional"))
    )
    (net (code "78") (name "/P9.31") (class "Default")
      (node (ref "BB.CAPE1") (pin "B9.31") (pinfunction "SPI1.SCK_B9.31") (pintype "bidirectional"))
      (node (ref "BB.CAPE1") (pin "T9.31") (pinfunction "SPI1.SCK_T9.31") (pintype "bidirectional"))
    )
    (net (code "79") (name "/P9.32") (class "Default")
      (node (ref "BB.CAPE1") (pin "B9.32") (pinfunction "AVDD.ADC_B9.32") (pintype "bidirectional"))
      (node (ref "BB.CAPE1") (pin "T9.32") (pinfunction "AVDD.ADC_T9.32") (pintype "bidirectional"))
    )
    (net (code "80") (name "/P9.33") (class "Default")
      (node (ref "BB.CAPE1") (pin "B9.33") (pinfunction "AIN4_B9.33") (pintype "bidirectional"))
      (node (ref "BB.CAPE1") (pin "T9.33") (pinfunction "AIN4_T9.33") (pintype "bidirectional"))
    )
    (net (code "81") (name "/P9.34") (class "Default")
      (node (ref "BB.CAPE1") (pin "B9.34") (pinfunction "AGND.ADC_B9.34") (pintype "bidirectional"))
      (node (ref "BB.CAPE1") (pin "T9.34") (pinfunction "AGND.ADC_T9.34") (pintype "bidirectional"))
    )
    (net (code "82") (name "/P9.35") (class "Default")
      (node (ref "BB.CAPE1") (pin "B9.35") (pinfunction "AIN6_B9.35") (pintype "bidirectional"))
      (node (ref "BB.CAPE1") (pin "T9.35") (pinfunction "AIN6_T9.35") (pintype "bidirectional"))
    )
    (net (code "83") (name "/P9.36") (class "Default")
      (node (ref "BB.CAPE1") (pin "B9.36") (pinfunction "AIN5_B9.36") (pintype "bidirectional"))
      (node (ref "BB.CAPE1") (pin "T9.36") (pinfunction "AIN5_T9.36") (pintype "bidirectional"))
    )
    (net (code "84") (name "/P9.37") (class "Default")
      (node (ref "BB.CAPE1") (pin "B9.37") (pinfunction "AIN2_B9.37") (pintype "bidirectional"))
      (node (ref "BB.CAPE1") (pin "T9.37") (pinfunction "AIN2_T9.37") (pintype "bidirectional"))
    )
    (net (code "85") (name "/P9.38") (class "Default")
      (node (ref "BB.CAPE1") (pin "B9.38") (pinfunction "AIN3_B9.38") (pintype "bidirectional"))
      (node (ref "BB.CAPE1") (pin "T9.38") (pinfunction "AIN3_T9.38") (pintype "bidirectional"))
    )
    (net (code "86") (name "/P9.39") (class "Default")
      (node (ref "BB.CAPE1") (pin "B9.39") (pinfunction "AIN0_B9.39") (pintype "bidirectional"))
      (node (ref "BB.CAPE1") (pin "T9.39") (pinfunction "AIN0_T9.39") (pintype "bidirectional"))
    )
    (net (code "87") (name "/P9.40") (class "Default")
      (node (ref "BB.CAPE1") (pin "B9.40") (pinfunction "AIN1_B9.40") (pintype "bidirectional"))
      (node (ref "BB.CAPE1") (pin "T9.40") (pinfunction "AIN1_T9.40") (pintype "bidirectional"))
    )
    (net (code "88") (name "/P9.41") (class "Default")
      (node (ref "BB.CAPE1") (pin "B9.41") (pinfunction "GPIO20_B9.41") (pintype "bidirectional"))
      (node (ref "BB.CAPE1") (pin "T9.41") (pinfunction "GPIO20_T9.41") (pintype "bidirectional"))
    )
    (net (code "89") (name "/P9.42") (class "Default")
      (node (ref "BB.CAPE1") (pin "B9.42") (pinfunction "ECAPPWM0_B9.42") (pintype "bidirectional"))
      (node (ref "BB.CAPE1") (pin "T9.42") (pinfunction "ECAPPWM0_T9.42") (pintype "bidirectional"))
    )
    (net (code "90") (name "/SCL") (class "Default")
      (node (ref "BB.CAPE1") (pin "B9.19") (pinfunction "I2C2.SCL_B9.19") (pintype "bidirectional"))
      (node (ref "BB.CAPE1") (pin "T9.19") (pinfunction "I2C2.SCL_T9.19") (pintype "bidirectional"))
      (node (ref "R10") (pin "1") (pinfunction "1_1") (pintype "bidirectional"))
      (node (ref "U1") (pin "6") (pinfunction "SCL_6") (pintype "bidirectional"))
    )
    (net (code "91") (name "/SDA") (class "Default")
      (node (ref "BB.CAPE1") (pin "B9.20") (pinfunction "I2C2.SDA_B9.20") (pintype "bidirectional"))
      (node (ref "BB.CAPE1") (pin "T9.20") (pinfunction "I2C2.SDA_T9.20") (pintype "bidirectional"))
      (node (ref "R9") (pin "1") (pinfunction "1_1") (pintype "bidirectional"))
      (node (ref "U1") (pin "5") (pinfunction "SDA_5") (pintype "bidirectional"))
    )
    (net (code "92") (name "/SYS.VOUT") (class "Default")
      (node (ref "BB.CAPE1") (pin "B9.7") (pinfunction "SYS.5V(1)_B9.7") (pintype "bidirectional"))
      (node (ref "BB.CAPE1") (pin "B9.8") (pinfunction "SYS.5V(2)_B9.8") (pintype "bidirectional"))
      (node (ref "BB.CAPE1") (pin "T9.7") (pinfunction "SYS.5V(1)_T9.7") (pintype "bidirectional"))
      (node (ref "BB.CAPE1") (pin "T9.8") (pinfunction "SYS.5V(2)_T9.8") (pintype "bidirectional"))
    )
    (net (code "93") (name "GND") (class "Default")
      (node (ref "BB.CAPE1") (pin "B8.1") (pinfunction "DGND1_B8.1") (pintype "bidirectional"))
      (node (ref "BB.CAPE1") (pin "B8.2") (pinfunction "DGND2_B8.2") (pintype "bidirectional"))
      (node (ref "BB.CAPE1") (pin "B9.1") (pinfunction "DGND1_B9.1") (pintype "bidirectional"))
      (node (ref "BB.CAPE1") (pin "B9.2") (pinfunction "DGND2_B9.2") (pintype "bidirectional"))
      (node (ref "BB.CAPE1") (pin "B9.43") (pinfunction "DGND3_B9.43") (pintype "bidirectional"))
      (node (ref "BB.CAPE1") (pin "B9.44") (pinfunction "DGND4_B9.44") (pintype "bidirectional"))
      (node (ref "BB.CAPE1") (pin "B9.45") (pinfunction "DGND5_B9.45") (pintype "bidirectional"))
      (node (ref "BB.CAPE1") (pin "B9.46") (pinfunction "DGND6_B9.46") (pintype "bidirectional"))
      (node (ref "BB.CAPE1") (pin "T8.1") (pinfunction "DGND1_T8.1") (pintype "bidirectional"))
      (node (ref "BB.CAPE1") (pin "T8.2") (pinfunction "DGND2_T8.2") (pintype "bidirectional"))
      (node (ref "BB.CAPE1") (pin "T9.1") (pinfunction "DGND1_T9.1") (pintype "bidirectional"))
      (node (ref "BB.CAPE1") (pin "T9.2") (pinfunction "DGND2_T9.2") (pintype "bidirectional"))
      (node (ref "BB.CAPE1") (pin "T9.43") (pinfunction "DGND3_T9.43") (pintype "bidirectional"))
      (node (ref "BB.CAPE1") (pin "T9.44") (pinfunction "DGND4_T9.44") (pintype "bidirectional"))
      (node (ref "BB.CAPE1") (pin "T9.45") (pinfunction "DGND5_T9.45") (pintype "bidirectional"))
      (node (ref "BB.CAPE1") (pin "T9.46") (pinfunction "DGND6_T9.46") (pintype "bidirectional"))
      (node (ref "C1") (pin "2") (pinfunction "2_2") (pintype "bidirectional"))
      (node (ref "C2") (pin "2") (pinfunction "2_2") (pintype "bidirectional"))
      (node (ref "C3") (pin "2") (pinfunction "2_2") (pintype "bidirectional"))
      (node (ref "C4") (pin "2") (pinfunction "2_2") (pintype "bidirectional"))
      (node (ref "C5") (pin "2") (pinfunction "2_2") (pintype "bidirectional"))
      (node (ref "C6") (pin "2") (pinfunction "2_2") (pintype "bidirectional"))
      (node (ref "C7") (pin "2") (pinfunction "2_2") (pintype "bidirectional"))
      (node (ref "C8") (pin "2") (pinfunction "2_2") (pintype "bidirectional"))
      (node (ref "C9") (pin "2") (pinfunction "2_2") (pintype "bidirectional"))
      (node (ref "D10") (pin "A") (pinfunction "ANODE_A") (pintype "bidirectional"))
      (node (ref "D12") (pin "A") (pinfunction "ANODE_A") (pintype "bidirectional"))
      (node (ref "D14") (pin "A") (pinfunction "ANODE_A") (pintype "bidirectional"))
      (node (ref "D16") (pin "A") (pinfunction "ANODE_A") (pintype "bidirectional"))
      (node (ref "D2") (pin "A") (pinfunction "ANODE_A") (pintype "bidirectional"))
      (node (ref "D4") (pin "A") (pinfunction "ANODE_A") (pintype "bidirectional"))
      (node (ref "D6") (pin "A") (pinfunction "ANODE_A") (pintype "bidirectional"))
      (node (ref "D8") (pin "A") (pinfunction "ANODE_A") (pintype "bidirectional"))
      (node (ref "JMP1") (pin "2") (pinfunction "2_2") (pintype "bidirectional"))
      (node (ref "M1") (pin "K") (pinfunction "K_K") (pintype "passive"))
      (node (ref "M2") (pin "K") (pinfunction "K_K") (pintype "passive"))
      (node (ref "M3") (pin "K") (pinfunction "K_K") (pintype "passive"))
      (node (ref "M4") (pin "K") (pinfunction "K_K") (pintype "passive"))
      (node (ref "R6") (pin "1") (pinfunction "1_1") (pintype "bidirectional"))
      (node (ref "SJ1") (pin "1") (pinfunction "1_1") (pintype "bidirectional"))
      (node (ref "U1") (pin "4") (pinfunction "VSS_4") (pintype "bidirectional"))
      (node (ref "U2") (pin "1") (pinfunction "GND1_1") (pintype "bidirectional"))
      (node (ref "U2") (pin "10") (pinfunction "GND2_10") (pintype "bidirectional"))
      (node (ref "U2") (pin "11") (pinfunction "GND3_11") (pintype "bidirectional"))
      (node (ref "U2") (pin "19") (pinfunction "SENSE.B_19") (pintype "bidirectional"))
      (node (ref "U2") (pin "2") (pinfunction "SENSE.A_2") (pintype "bidirectional"))
      (node (ref "U2") (pin "20") (pinfunction "GND4_20") (pintype "bidirectional"))
      (node (ref "U2") (pin "THERMAL.PAD") (pinfunction "THERMAL.PAD_THERMAL.PAD") (pintype "bidirectional"))
      (node (ref "U2") (pin "TV1") (pinfunction "THERMAL.PAD_TV1") (pintype "bidirectional"))
      (node (ref "U2") (pin "TV10") (pinfunction "THERMAL.PAD_TV10") (pintype "bidirectional"))
      (node (ref "U2") (pin "TV11") (pinfunction "THERMAL.PAD_TV11") (pintype "bidirectional"))
      (node (ref "U2") (pin "TV12") (pinfunction "THERMAL.PAD_TV12") (pintype "bidirectional"))
      (node (ref "U2") (pin "TV13") (pinfunction "THERMAL.PAD_TV13") (pintype "bidirectional"))
      (node (ref "U2") (pin "TV14") (pinfunction "THERMAL.PAD_TV14") (pintype "bidirectional"))
      (node (ref "U2") (pin "TV15") (pinfunction "THERMAL.PAD_TV15") (pintype "bidirectional"))
      (node (ref "U2") (pin "TV16") (pinfunction "THERMAL.PAD_TV16") (pintype "bidirectional"))
      (node (ref "U2") (pin "TV17") (pinfunction "THERMAL.PAD_TV17") (pintype "bidirectional"))
      (node (ref "U2") (pin "TV18") (pinfunction "THERMAL.PAD_TV18") (pintype "bidirectional"))
      (node (ref "U2") (pin "TV19") (pinfunction "THERMAL.PAD_TV19") (pintype "bidirectional"))
      (node (ref "U2") (pin "TV2") (pinfunction "THERMAL.PAD_TV2") (pintype "bidirectional"))
      (node (ref "U2") (pin "TV20") (pinfunction "THERMAL.PAD_TV20") (pintype "bidirectional"))
      (node (ref "U2") (pin "TV21") (pinfunction "THERMAL.PAD_TV21") (pintype "bidirectional"))
      (node (ref "U2") (pin "TV3") (pinfunction "THERMAL.PAD_TV3") (pintype "bidirectional"))
      (node (ref "U2") (pin "TV4") (pinfunction "THERMAL.PAD_TV4") (pintype "bidirectional"))
      (node (ref "U2") (pin "TV5") (pinfunction "THERMAL.PAD_TV5") (pintype "bidirectional"))
      (node (ref "U2") (pin "TV6") (pinfunction "THERMAL.PAD_TV6") (pintype "bidirectional"))
      (node (ref "U2") (pin "TV7") (pinfunction "THERMAL.PAD_TV7") (pintype "bidirectional"))
      (node (ref "U2") (pin "TV8") (pinfunction "THERMAL.PAD_TV8") (pintype "bidirectional"))
      (node (ref "U2") (pin "TV9") (pinfunction "THERMAL.PAD_TV9") (pintype "bidirectional"))
      (node (ref "U3") (pin "1") (pinfunction "GND1_1") (pintype "bidirectional"))
      (node (ref "U3") (pin "10") (pinfunction "GND2_10") (pintype "bidirectional"))
      (node (ref "U3") (pin "11") (pinfunction "GND3_11") (pintype "bidirectional"))
      (node (ref "U3") (pin "19") (pinfunction "SENSE.B_19") (pintype "bidirectional"))
      (node (ref "U3") (pin "2") (pinfunction "SENSE.A_2") (pintype "bidirectional"))
      (node (ref "U3") (pin "20") (pinfunction "GND4_20") (pintype "bidirectional"))
      (node (ref "U3") (pin "THERMAL.PAD") (pinfunction "THERMAL.PAD_THERMAL.PAD") (pintype "bidirectional"))
      (node (ref "U3") (pin "TV1") (pinfunction "THERMAL.PAD_TV1") (pintype "bidirectional"))
      (node (ref "U3") (pin "TV10") (pinfunction "THERMAL.PAD_TV10") (pintype "bidirectional"))
      (node (ref "U3") (pin "TV11") (pinfunction "THERMAL.PAD_TV11") (pintype "bidirectional"))
      (node (ref "U3") (pin "TV12") (pinfunction "THERMAL.PAD_TV12") (pintype "bidirectional"))
      (node (ref "U3") (pin "TV13") (pinfunction "THERMAL.PAD_TV13") (pintype "bidirectional"))
      (node (ref "U3") (pin "TV14") (pinfunction "THERMAL.PAD_TV14") (pintype "bidirectional"))
      (node (ref "U3") (pin "TV15") (pinfunction "THERMAL.PAD_TV15") (pintype "bidirectional"))
      (node (ref "U3") (pin "TV16") (pinfunction "THERMAL.PAD_TV16") (pintype "bidirectional"))
      (node (ref "U3") (pin "TV17") (pinfunction "THERMAL.PAD_TV17") (pintype "bidirectional"))
      (node (ref "U3") (pin "TV18") (pinfunction "THERMAL.PAD_TV18") (pintype "bidirectional"))
      (node (ref "U3") (pin "TV19") (pinfunction "THERMAL.PAD_TV19") (pintype "bidirectional"))
      (node (ref "U3") (pin "TV2") (pinfunction "THERMAL.PAD_TV2") (pintype "bidirectional"))
      (node (ref "U3") (pin "TV20") (pinfunction "THERMAL.PAD_TV20") (pintype "bidirectional"))
      (node (ref "U3") (pin "TV21") (pinfunction "THERMAL.PAD_TV21") (pintype "bidirectional"))
      (node (ref "U3") (pin "TV3") (pinfunction "THERMAL.PAD_TV3") (pintype "bidirectional"))
      (node (ref "U3") (pin "TV4") (pinfunction "THERMAL.PAD_TV4") (pintype "bidirectional"))
      (node (ref "U3") (pin "TV5") (pinfunction "THERMAL.PAD_TV5") (pintype "bidirectional"))
      (node (ref "U3") (pin "TV6") (pinfunction "THERMAL.PAD_TV6") (pintype "bidirectional"))
      (node (ref "U3") (pin "TV7") (pinfunction "THERMAL.PAD_TV7") (pintype "bidirectional"))
      (node (ref "U3") (pin "TV8") (pinfunction "THERMAL.PAD_TV8") (pintype "bidirectional"))
      (node (ref "U3") (pin "TV9") (pinfunction "THERMAL.PAD_TV9") (pintype "bidirectional"))
      (node (ref "U4") (pin "GND") (pinfunction "GND_GND") (pintype "bidirectional"))
      (node (ref "U4") (pin "IN1") (pinfunction "IN1_IN1") (pintype "bidirectional"))
      (node (ref "U4") (pin "IN2") (pinfunction "IN2_IN2") (pintype "bidirectional"))
      (node (ref "U5") (pin "GND") (pinfunction "GND_GND") (pintype "bidirectional"))
      (node (ref "U5") (pin "IN1") (pinfunction "IN1_IN1") (pintype "bidirectional"))
      (node (ref "U5") (pin "IN2") (pinfunction "IN2_IN2") (pintype "bidirectional"))
      (node (ref "U6") (pin "GND") (pinfunction "GND_GND") (pintype "bidirectional"))
      (node (ref "U6") (pin "IN1") (pinfunction "IN1_IN1") (pintype "bidirectional"))
      (node (ref "U6") (pin "IN2") (pinfunction "IN2_IN2") (pintype "bidirectional"))
      (node (ref "U7") (pin "GND") (pinfunction "GND_GND") (pintype "bidirectional"))
      (node (ref "U7") (pin "IN1") (pinfunction "IN1_IN1") (pintype "bidirectional"))
      (node (ref "U7") (pin "IN2") (pinfunction "IN2_IN2") (pintype "bidirectional"))
      (node (ref "X1") (pin "5") (pinfunction "5_5") (pintype "bidirectional"))
    )
    (net (code "94") (name "Net-(M1-PadA)") (class "Default")
      (node (ref "M1") (pin "A") (pinfunction "A_A") (pintype "passive"))
      (node (ref "R1") (pin "2") (pinfunction "2_2") (pintype "bidirectional"))
    )
    (net (code "95") (name "Net-(M2-PadA)") (class "Default")
      (node (ref "M2") (pin "A") (pinfunction "A_A") (pintype "passive"))
      (node (ref "R2") (pin "2") (pinfunction "2_2") (pintype "bidirectional"))
    )
    (net (code "96") (name "Net-(M3-PadA)") (class "Default")
      (node (ref "M3") (pin "A") (pinfunction "A_A") (pintype "passive"))
      (node (ref "R3") (pin "1") (pinfunction "1_1") (pintype "bidirectional"))
    )
    (net (code "97") (name "Net-(M4-PadA)") (class "Default")
      (node (ref "M4") (pin "A") (pinfunction "A_A") (pintype "passive"))
      (node (ref "R4") (pin "1") (pinfunction "1_1") (pintype "bidirectional"))
    )
    (net (code "98") (name "Net-(U1-A0)") (class "Default")
      (node (ref "R5") (pin "2") (pinfunction "2_2") (pintype "bidirectional"))
      (node (ref "SJ1") (pin "2") (pinfunction "2_2") (pintype "bidirectional"))
      (node (ref "U1") (pin "1") (pinfunction "A0_1") (pintype "bidirectional"))
    )
    (net (code "99") (name "Net-(U1-A1)") (class "Default")
      (node (ref "R6") (pin "2") (pinfunction "2_2") (pintype "bidirectional"))
      (node (ref "SJ2") (pin "2") (pinfunction "2_2") (pintype "bidirectional"))
      (node (ref "U1") (pin "2") (pinfunction "A1_2") (pintype "bidirectional"))
    )
    (net (code "100") (name "Net-(U1-A2)") (class "Default")
      (node (ref "R7") (pin "2") (pinfunction "2_2") (pintype "bidirectional"))
      (node (ref "U1") (pin "3") (pinfunction "A2_3") (pintype "bidirectional"))
    )
    (net (code "101") (name "Net-(U1-WP)") (class "Default")
      (node (ref "JMP1") (pin "1") (pinfunction "1_1") (pintype "bidirectional"))
      (node (ref "R8") (pin "1") (pinfunction "1_1") (pintype "bidirectional"))
      (node (ref "U1") (pin "7") (pinfunction "WP_7") (pintype "bidirectional"))
    )
    (net (code "102") (name "VCC") (class "Default")
      (node (ref "BB.CAPE1") (pin "B9.3") (pinfunction "VDD.3V3(1)_B9.3") (pintype "bidirectional"))
      (node (ref "BB.CAPE1") (pin "B9.4") (pinfunction "VDD.3V3(2)_B9.4") (pintype "bidirectional"))
      (node (ref "BB.CAPE1") (pin "T9.3") (pinfunction "VDD.3V3(1)_T9.3") (pintype "bidirectional"))
      (node (ref "BB.CAPE1") (pin "T9.4") (pinfunction "VDD.3V3(2)_T9.4") (pintype "bidirectional"))
      (node (ref "C1") (pin "1") (pinfunction "1_1") (pintype "bidirectional"))
      (node (ref "C2") (pin "1") (pinfunction "1_1") (pintype "bidirectional"))
      (node (ref "C3") (pin "1") (pinfunction "1_1") (pintype "bidirectional"))
      (node (ref "C4") (pin "1") (pinfunction "1_1") (pintype "bidirectional"))
      (node (ref "C5") (pin "1") (pinfunction "1_1") (pintype "bidirectional"))
      (node (ref "R10") (pin "2") (pinfunction "2_2") (pintype "bidirectional"))
      (node (ref "R5") (pin "1") (pinfunction "1_1") (pintype "bidirectional"))
      (node (ref "R7") (pin "1") (pinfunction "1_1") (pintype "bidirectional"))
      (node (ref "R8") (pin "2") (pinfunction "2_2") (pintype "bidirectional"))
      (node (ref "R9") (pin "2") (pinfunction "2_2") (pintype "bidirectional"))
      (node (ref "SJ2") (pin "1") (pinfunction "1_1") (pintype "bidirectional"))
      (node (ref "U1") (pin "8") (pinfunction "VCC_8") (pintype "bidirectional"))
      (node (ref "U4") (pin "VCC") (pinfunction "VCC_VCC") (pintype "bidirectional"))
      (node (ref "U5") (pin "VCC") (pinfunction "VCC_VCC") (pintype "bidirectional"))
      (node (ref "U6") (pin "VCC") (pinfunction "VCC_VCC") (pintype "bidirectional"))
      (node (ref "U7") (pin "VCC") (pinfunction "VCC_VCC") (pintype "bidirectional"))
    )
    (net (code "103") (name "VIN") (class "Default")
      (node (ref "C6") (pin "1") (pinfunction "1_1") (pintype "bidirectional"))
      (node (ref "C7") (pin "1") (pinfunction "1_1") (pintype "bidirectional"))
      (node (ref "D1") (pin "K") (pinfunction "CATHODE_K") (pintype "bidirectional"))
      (node (ref "D11") (pin "K") (pinfunction "CATHODE_K") (pintype "bidirectional"))
      (node (ref "D13") (pin "K") (pinfunction "CATHODE_K") (pintype "bidirectional"))
      (node (ref "D15") (pin "K") (pinfunction "CATHODE_K") (pintype "bidirectional"))
      (node (ref "D3") (pin "K") (pinfunction "CATHODE_K") (pintype "bidirectional"))
      (node (ref "D5") (pin "K") (pinfunction "CATHODE_K") (pintype "bidirectional"))
      (node (ref "D7") (pin "K") (pinfunction "CATHODE_K") (pintype "bidirectional"))
      (node (ref "D9") (pin "K") (pinfunction "CATHODE_K") (pintype "bidirectional"))
      (node (ref "U2") (pin "6") (pinfunction "VS_6") (pintype "bidirectional"))
      (node (ref "U3") (pin "6") (pinfunction "VS_6") (pintype "bidirectional"))
      (node (ref "X1") (pin "6") (pinfunction "6_6") (pintype "bidirectional"))
    )
    (net (code "104") (name "unconnected-(FUD1-PadP$1)") (class "Default")
      (node (ref "FUD1") (pin "P$1") (pinfunction "P$1_P$1") (pintype "no_connect"))
    )
    (net (code "105") (name "unconnected-(FUD2-PadP$1)") (class "Default")
      (node (ref "FUD2") (pin "P$1") (pinfunction "P$1_P$1") (pintype "no_connect"))
    )
    (net (code "106") (name "unconnected-(FUD3-PadP$1)") (class "Default")
      (node (ref "FUD3") (pin "P$1") (pinfunction "P$1_P$1") (pintype "no_connect"))
    )
    (net (code "107") (name "unconnected-(FUD4-PadP$1)") (class "Default")
      (node (ref "FUD4") (pin "P$1") (pinfunction "P$1_P$1") (pintype "no_connect"))
    )
    (net (code "108") (name "unconnected-(FUD5-PadP$1)") (class "Default")
      (node (ref "FUD5") (pin "P$1") (pinfunction "P$1_P$1") (pintype "no_connect"))
    )
    (net (code "109") (name "unconnected-(FUD6-PadP$1)") (class "Default")
      (node (ref "FUD6") (pin "P$1") (pinfunction "P$1_P$1") (pintype "no_connect"))
    )
    (net (code "110") (name "unconnected-(U2-NC1-Pad3)") (class "Default")
      (node (ref "U2") (pin "3") (pinfunction "NC1_3") (pintype "bidirectional"))
    )
    (net (code "111") (name "unconnected-(U2-NC2-Pad18)") (class "Default")
      (node (ref "U2") (pin "18") (pinfunction "NC2_18") (pintype "bidirectional"))
    )
    (net (code "112") (name "unconnected-(U3-NC1-Pad3)") (class "Default")
      (node (ref "U3") (pin "3") (pinfunction "NC1_3") (pintype "bidirectional"))
    )
    (net (code "113") (name "unconnected-(U3-NC2-Pad18)") (class "Default")
      (node (ref "U3") (pin "18") (pinfunction "NC2_18") (pintype "bidirectional"))
    )
  )
)
